# BrushlessDCMotorController.net
KiCad netlist of a schematic drawn in EAGLE
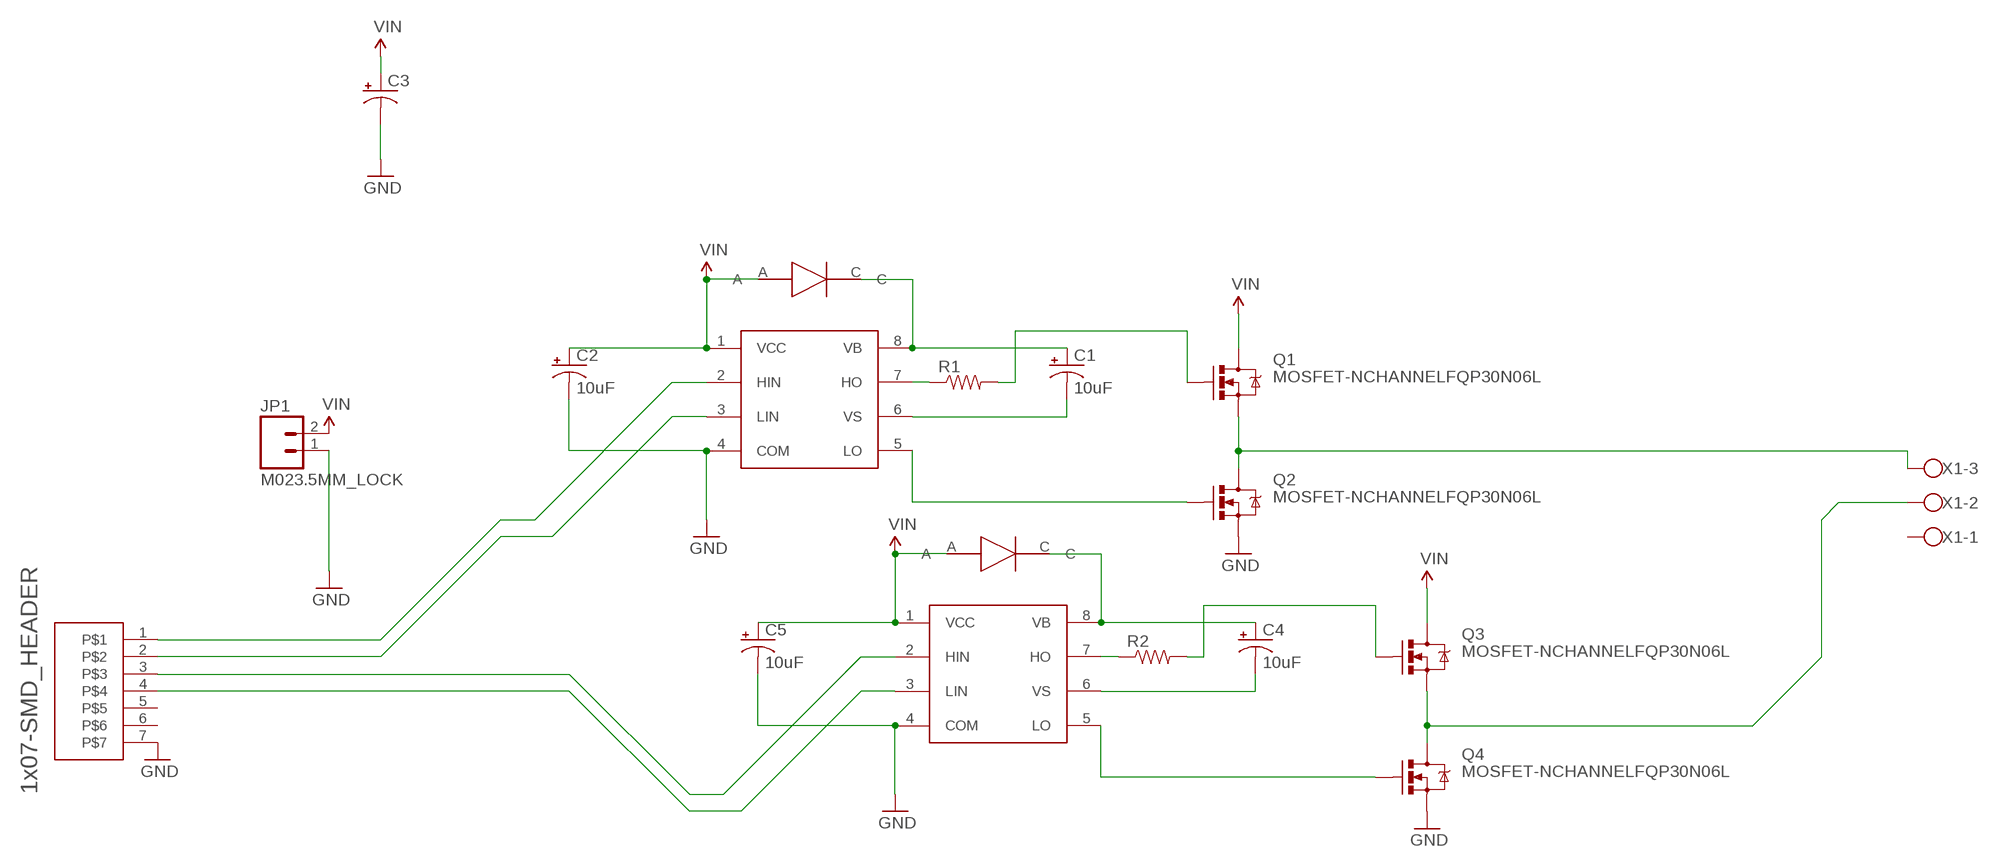
[diagram p0: schematic, sheet 1]

(export (version "E")
  (design (tool "Eeschema 10.0.6"))
  (components
    (comp (ref "C1")
      (value "10uF")
      (footprint "eagle-import:EIA3216")
      (libsource (lib "eagle-import") (part "10UF-16V-10%(TANT)"))
    )
    (comp (ref "C2")
      (value "10uF")
      (footprint "eagle-import:EIA3216")
      (libsource (lib "eagle-import") (part "10UF-16V-10%(TANT)"))
    )
    (comp (ref "C3")
      (value "CAP_POLD")
      (footprint "eagle-import:PANASONIC_D")
      (libsource (lib "eagle-import") (part "CAP_POLD"))
    )
    (comp (ref "C4")
      (value "10uF")
      (footprint "eagle-import:EIA3216")
      (libsource (lib "eagle-import") (part "10UF-16V-10%(TANT)"))
    )
    (comp (ref "C5")
      (value "10uF")
      (footprint "eagle-import:EIA3216")
      (libsource (lib "eagle-import") (part "10UF-16V-10%(TANT)"))
    )
    (comp (ref "JP1")
      (value "M023.5MM_LOCK")
      (footprint "eagle-import:SCREWTERMINAL-3.5MM-2_LOCK")
      (libsource (lib "eagle-import") (part "M023.5MM_LOCK"))
    )
    (comp (ref "Q1")
      (value "MOSFET-NCHANNELFQP30N06L")
      (footprint "eagle-import:TO220V")
      (libsource (lib "eagle-import") (part "MOSFET-NCHANNELFQP30N06L"))
    )
    (comp (ref "Q2")
      (value "MOSFET-NCHANNELFQP30N06L")
      (footprint "eagle-import:TO220V")
      (libsource (lib "eagle-import") (part "MOSFET-NCHANNELFQP30N06L"))
    )
    (comp (ref "Q3")
      (value "MOSFET-NCHANNELFQP30N06L")
      (footprint "eagle-import:TO220V")
      (libsource (lib "eagle-import") (part "MOSFET-NCHANNELFQP30N06L"))
    )
    (comp (ref "Q4")
      (value "MOSFET-NCHANNELFQP30N06L")
      (footprint "eagle-import:TO220V")
      (libsource (lib "eagle-import") (part "MOSFET-NCHANNELFQP30N06L"))
    )
    (comp (ref "R1")
      (value "RESISTOR0805-RES")
      (footprint "eagle-import:0805")
      (libsource (lib "eagle-import") (part "RESISTOR0805-RES"))
    )
    (comp (ref "R2")
      (value "RESISTOR0805-RES")
      (footprint "eagle-import:0805")
      (libsource (lib "eagle-import") (part "RESISTOR0805-RES"))
    )
    (comp (ref "U$1")
      (value "IR2101")
      (footprint "eagle-import:SO08")
      (libsource (lib "eagle-import") (part "IR2101"))
    )
    (comp (ref "U$2")
      (value "DFLS1150")
      (footprint "eagle-import:2SMD_FLAT_LEAD")
      (libsource (lib "eagle-import") (part "DFLS1150"))
    )
    (comp (ref "U$3")
      (value "1X07-SMD_HEADER")
      (footprint "eagle-import:1X07-SMD_HEADER")
      (libsource (lib "eagle-import") (part "1X07-SMD_HEADER"))
    )
    (comp (ref "U$4")
      (value "IR2101")
      (footprint "eagle-import:SO08")
      (libsource (lib "eagle-import") (part "IR2101"))
    )
    (comp (ref "U$5")
      (value "DFLS1150")
      (footprint "eagle-import:2SMD_FLAT_LEAD")
      (libsource (lib "eagle-import") (part "DFLS1150"))
    )
    (comp (ref "X1")
      (value "W239-103")
      (footprint "eagle-import:W239-103")
      (fields (field (name "MPN") "239-103"))
      (libsource (lib "eagle-import") (part "W239-103"))
    )
  )
  (nets
    (net (code "1") (name "GND") (class "Default")
      (node (ref "C2") (pin "C") (pinfunction "-_C") (pintype "passive"))
      (node (ref "C3") (pin "-") (pinfunction "-_-") (pintype "passive"))
      (node (ref "C5") (pin "C") (pinfunction "-_C") (pintype "passive"))
      (node (ref "JP1") (pin "1") (pinfunction "1_1") (pintype "passive"))
      (node (ref "Q2") (pin "3") (pinfunction "S_3") (pintype "passive"))
      (node (ref "Q4") (pin "3") (pinfunction "S_3") (pintype "passive"))
      (node (ref "U$1") (pin "4") (pinfunction "COM_4") (pintype "bidirectional"))
      (node (ref "U$3") (pin "7") (pinfunction "P$7_7") (pintype "bidirectional"))
      (node (ref "U$4") (pin "4") (pinfunction "COM_4") (pintype "bidirectional"))
    )
    (net (code "2") (name "Net-(C1-+)") (class "Default")
      (node (ref "C1") (pin "A") (pinfunction "+_A") (pintype "passive"))
      (node (ref "U$1") (pin "8") (pinfunction "VB_8") (pintype "bidirectional"))
      (node (ref "U$2") (pin "C") (pinfunction "C_C") (pintype "bidirectional"))
    )
    (net (code "3") (name "Net-(C1--)") (class "Default")
      (node (ref "C1") (pin "C") (pinfunction "-_C") (pintype "passive"))
      (node (ref "U$1") (pin "6") (pinfunction "VS_6") (pintype "bidirectional"))
    )
    (net (code "4") (name "Net-(C4-+)") (class "Default")
      (node (ref "C4") (pin "A") (pinfunction "+_A") (pintype "passive"))
      (node (ref "U$4") (pin "8") (pinfunction "VB_8") (pintype "bidirectional"))
      (node (ref "U$5") (pin "C") (pinfunction "C_C") (pintype "bidirectional"))
    )
    (net (code "5") (name "Net-(C4--)") (class "Default")
      (node (ref "C4") (pin "C") (pinfunction "-_C") (pintype "passive"))
      (node (ref "U$4") (pin "6") (pinfunction "VS_6") (pintype "bidirectional"))
    )
    (net (code "6") (name "Net-(Q1-G)") (class "Default")
      (node (ref "Q1") (pin "1") (pinfunction "G_1") (pintype "passive"))
      (node (ref "R1") (pin "2") (pinfunction "2_2") (pintype "passive"))
    )
    (net (code "7") (name "Net-(Q1-S)") (class "Default")
      (node (ref "Q1") (pin "3") (pinfunction "S_3") (pintype "passive"))
      (node (ref "Q2") (pin "2") (pinfunction "D_2") (pintype "passive"))
      (node (ref "X1") (pin "3") (pinfunction "KL_3") (pintype "passive"))
    )
    (net (code "8") (name "Net-(Q2-G)") (class "Default")
      (node (ref "Q2") (pin "1") (pinfunction "G_1") (pintype "passive"))
      (node (ref "U$1") (pin "5") (pinfunction "LO_5") (pintype "bidirectional"))
    )
    (net (code "9") (name "Net-(Q3-G)") (class "Default")
      (node (ref "Q3") (pin "1") (pinfunction "G_1") (pintype "passive"))
      (node (ref "R2") (pin "2") (pinfunction "2_2") (pintype "passive"))
    )
    (net (code "10") (name "Net-(Q3-S)") (class "Default")
      (node (ref "Q3") (pin "3") (pinfunction "S_3") (pintype "passive"))
      (node (ref "Q4") (pin "2") (pinfunction "D_2") (pintype "passive"))
      (node (ref "X1") (pin "2") (pinfunction "KL_2") (pintype "passive"))
    )
    (net (code "11") (name "Net-(Q4-G)") (class "Default")
      (node (ref "Q4") (pin "1") (pinfunction "G_1") (pintype "passive"))
      (node (ref "U$4") (pin "5") (pinfunction "LO_5") (pintype "bidirectional"))
    )
    (net (code "12") (name "Net-(U$1-HIN)") (class "Default")
      (node (ref "U$1") (pin "2") (pinfunction "HIN_2") (pintype "bidirectional"))
      (node (ref "U$3") (pin "1") (pinfunction "P$1_1") (pintype "bidirectional"))
    )
    (net (code "13") (name "Net-(U$1-HO)") (class "Default")
      (node (ref "R1") (pin "1") (pinfunction "1_1") (pintype "passive"))
      (node (ref "U$1") (pin "7") (pinfunction "HO_7") (pintype "bidirectional"))
    )
    (net (code "14") (name "Net-(U$1-LIN)") (class "Default")
      (node (ref "U$1") (pin "3") (pinfunction "LIN_3") (pintype "bidirectional"))
      (node (ref "U$3") (pin "2") (pinfunction "P$2_2") (pintype "bidirectional"))
    )
    (net (code "15") (name "Net-(U$3-P$3)") (class "Default")
      (node (ref "U$3") (pin "3") (pinfunction "P$3_3") (pintype "bidirectional"))
      (node (ref "U$4") (pin "2") (pinfunction "HIN_2") (pintype "bidirectional"))
    )
    (net (code "16") (name "Net-(U$3-P$4)") (class "Default")
      (node (ref "U$3") (pin "4") (pinfunction "P$4_4") (pintype "bidirectional"))
      (node (ref "U$4") (pin "3") (pinfunction "LIN_3") (pintype "bidirectional"))
    )
    (net (code "17") (name "Net-(U$4-HO)") (class "Default")
      (node (ref "R2") (pin "1") (pinfunction "1_1") (pintype "passive"))
      (node (ref "U$4") (pin "7") (pinfunction "HO_7") (pintype "bidirectional"))
    )
    (net (code "18") (name "VIN") (class "Default")
      (node (ref "C2") (pin "A") (pinfunction "+_A") (pintype "passive"))
      (node (ref "C3") (pin "+") (pinfunction "+_+") (pintype "passive"))
      (node (ref "C5") (pin "A") (pinfunction "+_A") (pintype "passive"))
      (node (ref "JP1") (pin "2") (pinfunction "2_2") (pintype "passive"))
      (node (ref "Q1") (pin "2") (pinfunction "D_2") (pintype "passive"))
      (node (ref "Q3") (pin "2") (pinfunction "D_2") (pintype "passive"))
      (node (ref "U$1") (pin "1") (pinfunction "VCC_1") (pintype "bidirectional"))
      (node (ref "U$2") (pin "A") (pinfunction "A_A") (pintype "bidirectional"))
      (node (ref "U$4") (pin "1") (pinfunction "VCC_1") (pintype "bidirectional"))
      (node (ref "U$5") (pin "A") (pinfunction "A_A") (pintype "bidirectional"))
    )
    (net (code "19") (name "unconnected-(U$3-P$5-Pad5)") (class "Default")
      (node (ref "U$3") (pin "5") (pinfunction "P$5_5") (pintype "bidirectional"))
    )
    (net (code "20") (name "unconnected-(U$3-P$6-Pad6)") (class "Default")
      (node (ref "U$3") (pin "6") (pinfunction "P$6_6") (pintype "bidirectional"))
    )
    (net (code "21") (name "unconnected-(X1A-KL-Pad1)") (class "Default")
      (node (ref "X1") (pin "1") (pinfunction "KL_1") (pintype "passive"))
    )
  )
)
